# drivers.net
KiCad netlist of a schematic drawn in Altium Designer
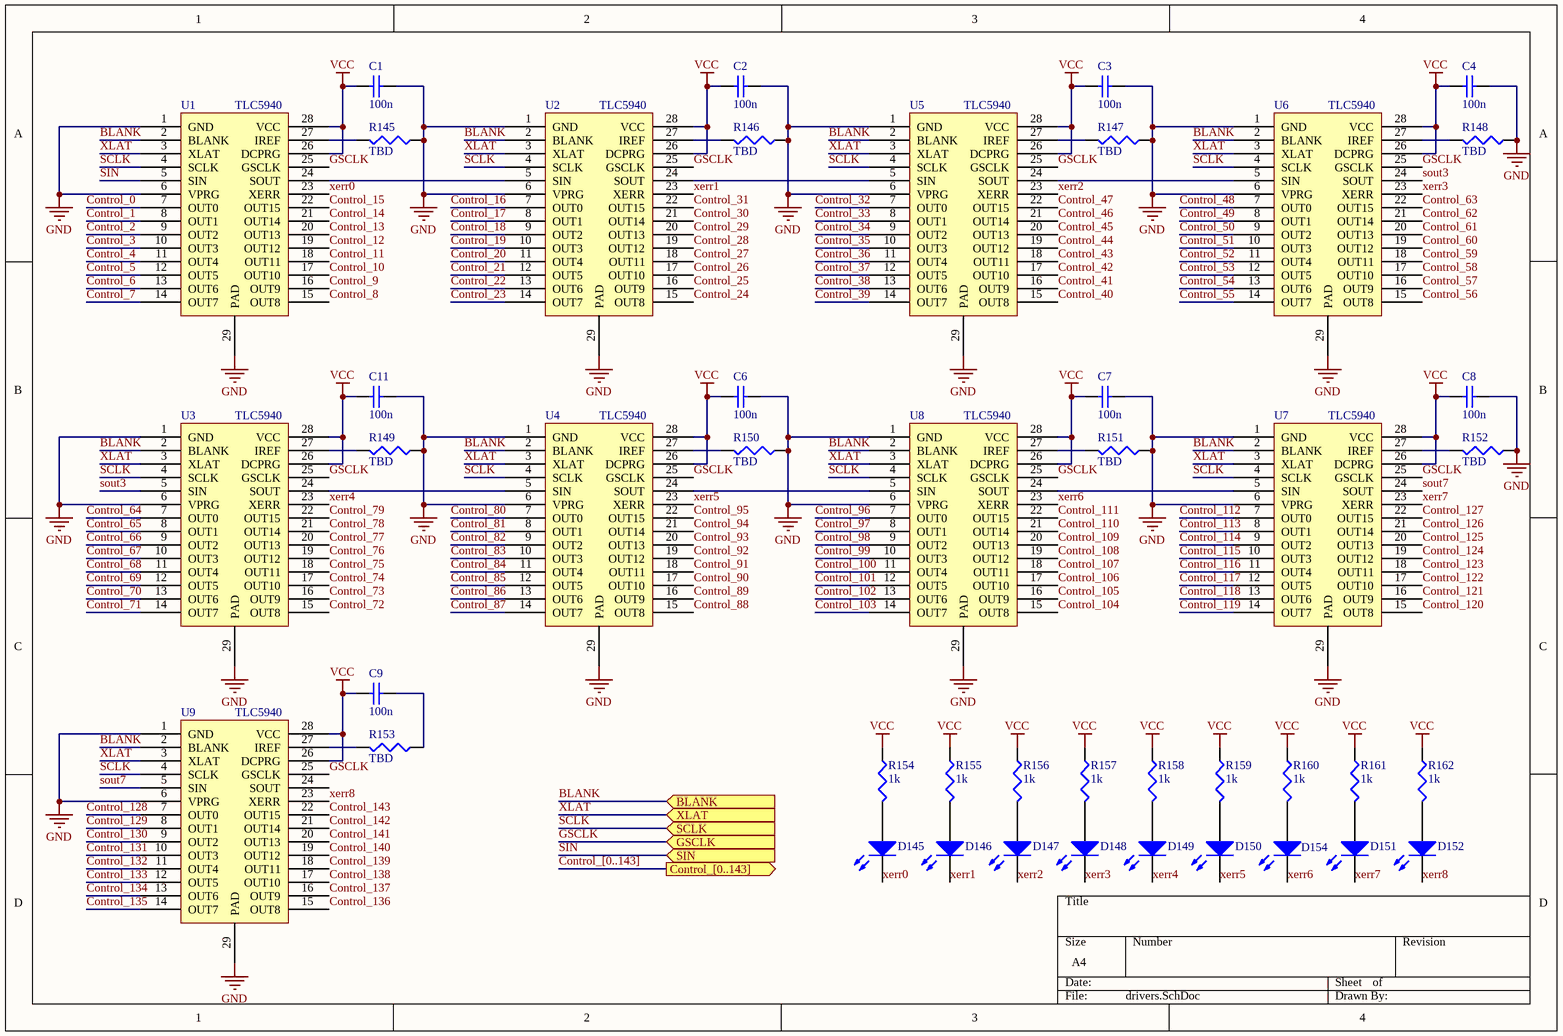
[diagram p0: drivers.SchDoc]

(export (version "E")
  (design (tool "Eeschema 10.0.6"))
  (components
    (comp (ref "C1")
      (value "100n")
      (footprint "1608[0603]")
      (description "Capacitor (Semiconductor SIM Model)")
      (fields (field (name "Comment") "Cap Semi") (field (name "PUBLISHER") "Altium Limited"))
      (libsource (lib "Miscellaneous Devices") (part "Cap Semi"))
    )
    (comp (ref "C2")
      (value "100n")
      (footprint "1608[0603]")
      (description "Capacitor (Semiconductor SIM Model)")
      (fields (field (name "Comment") "Cap Semi") (field (name "PUBLISHER") "Altium Limited"))
      (libsource (lib "Miscellaneous Devices") (part "Cap Semi"))
    )
    (comp (ref "C3")
      (value "100n")
      (footprint "1608[0603]")
      (description "Capacitor (Semiconductor SIM Model)")
      (fields (field (name "Comment") "Cap Semi") (field (name "PUBLISHER") "Altium Limited"))
      (libsource (lib "Miscellaneous Devices") (part "Cap Semi"))
    )
    (comp (ref "C4")
      (value "100n")
      (footprint "1608[0603]")
      (description "Capacitor (Semiconductor SIM Model)")
      (fields (field (name "Comment") "Cap Semi") (field (name "PUBLISHER") "Altium Limited"))
      (libsource (lib "Miscellaneous Devices") (part "Cap Semi"))
    )
    (comp (ref "C6")
      (value "100n")
      (footprint "1608[0603]")
      (description "Capacitor (Semiconductor SIM Model)")
      (fields (field (name "Comment") "Cap Semi") (field (name "PUBLISHER") "Altium Limited"))
      (libsource (lib "Miscellaneous Devices") (part "Cap Semi"))
    )
    (comp (ref "C7")
      (value "100n")
      (footprint "1608[0603]")
      (description "Capacitor (Semiconductor SIM Model)")
      (fields (field (name "Comment") "Cap Semi") (field (name "PUBLISHER") "Altium Limited"))
      (libsource (lib "Miscellaneous Devices") (part "Cap Semi"))
    )
    (comp (ref "C8")
      (value "100n")
      (footprint "1608[0603]")
      (description "Capacitor (Semiconductor SIM Model)")
      (fields (field (name "Comment") "Cap Semi") (field (name "PUBLISHER") "Altium Limited"))
      (libsource (lib "Miscellaneous Devices") (part "Cap Semi"))
    )
    (comp (ref "C9")
      (value "100n")
      (footprint "1608[0603]")
      (description "Capacitor (Semiconductor SIM Model)")
      (fields (field (name "Comment") "Cap Semi") (field (name "PUBLISHER") "Altium Limited"))
      (libsource (lib "Miscellaneous Devices") (part "Cap Semi"))
    )
    (comp (ref "C11")
      (value "100n")
      (footprint "1608[0603]")
      (description "Capacitor (Semiconductor SIM Model)")
      (fields (field (name "Comment") "Cap Semi") (field (name "PUBLISHER") "Altium Limited"))
      (libsource (lib "Miscellaneous Devices") (part "Cap Semi"))
    )
    (comp (ref "D145")
      (value "LED0")
      (footprint "J1-0603")
      (description "Typical INFRARED GaAs LED")
      (fields (field (name "PUBLISHER") "Altium Limited"))
      (libsource (lib "Miscellaneous Devices") (part "LED0"))
    )
    (comp (ref "D146")
      (value "LED0")
      (footprint "J1-0603")
      (description "Typical INFRARED GaAs LED")
      (fields (field (name "PUBLISHER") "Altium Limited"))
      (libsource (lib "Miscellaneous Devices") (part "LED0"))
    )
    (comp (ref "D147")
      (value "LED0")
      (footprint "J1-0603")
      (description "Typical INFRARED GaAs LED")
      (fields (field (name "PUBLISHER") "Altium Limited"))
      (libsource (lib "Miscellaneous Devices") (part "LED0"))
    )
    (comp (ref "D148")
      (value "LED0")
      (footprint "J1-0603")
      (description "Typical INFRARED GaAs LED")
      (fields (field (name "PUBLISHER") "Altium Limited"))
      (libsource (lib "Miscellaneous Devices") (part "LED0"))
    )
    (comp (ref "D149")
      (value "LED0")
      (footprint "J1-0603")
      (description "Typical INFRARED GaAs LED")
      (fields (field (name "PUBLISHER") "Altium Limited"))
      (libsource (lib "Miscellaneous Devices") (part "LED0"))
    )
    (comp (ref "D150")
      (value "LED0")
      (footprint "J1-0603")
      (description "Typical INFRARED GaAs LED")
      (fields (field (name "PUBLISHER") "Altium Limited"))
      (libsource (lib "Miscellaneous Devices") (part "LED0"))
    )
    (comp (ref "D151")
      (value "LED0")
      (footprint "J1-0603")
      (description "Typical INFRARED GaAs LED")
      (fields (field (name "PUBLISHER") "Altium Limited"))
      (libsource (lib "Miscellaneous Devices") (part "LED0"))
    )
    (comp (ref "D152")
      (value "LED0")
      (footprint "J1-0603")
      (description "Typical INFRARED GaAs LED")
      (fields (field (name "PUBLISHER") "Altium Limited"))
      (libsource (lib "Miscellaneous Devices") (part "LED0"))
    )
    (comp (ref "D154")
      (value "LED0")
      (footprint "J1-0603")
      (description "Typical INFRARED GaAs LED")
      (fields (field (name "PUBLISHER") "Altium Limited"))
      (libsource (lib "Miscellaneous Devices") (part "LED0"))
    )
    (comp (ref "R145")
      (value "TBD")
      (footprint "J1-0603")
      (description "Resistor")
      (fields (field (name "Comment") "Res3") (field (name "PUBLISHER") "Altium Limited"))
      (libsource (lib "Miscellaneous Devices") (part "Res3"))
    )
    (comp (ref "R146")
      (value "TBD")
      (footprint "J1-0603")
      (description "Resistor")
      (fields (field (name "Comment") "Res3") (field (name "PUBLISHER") "Altium Limited"))
      (libsource (lib "Miscellaneous Devices") (part "Res3"))
    )
    (comp (ref "R147")
      (value "TBD")
      (footprint "J1-0603")
      (description "Resistor")
      (fields (field (name "Comment") "Res3") (field (name "PUBLISHER") "Altium Limited"))
      (libsource (lib "Miscellaneous Devices") (part "Res3"))
    )
    (comp (ref "R148")
      (value "TBD")
      (footprint "J1-0603")
      (description "Resistor")
      (fields (field (name "Comment") "Res3") (field (name "PUBLISHER") "Altium Limited"))
      (libsource (lib "Miscellaneous Devices") (part "Res3"))
    )
    (comp (ref "R149")
      (value "TBD")
      (footprint "J1-0603")
      (description "Resistor")
      (fields (field (name "Comment") "Res3") (field (name "PUBLISHER") "Altium Limited"))
      (libsource (lib "Miscellaneous Devices") (part "Res3"))
    )
    (comp (ref "R150")
      (value "TBD")
      (footprint "J1-0603")
      (description "Resistor")
      (fields (field (name "Comment") "Res3") (field (name "PUBLISHER") "Altium Limited"))
      (libsource (lib "Miscellaneous Devices") (part "Res3"))
    )
    (comp (ref "R151")
      (value "TBD")
      (footprint "J1-0603")
      (description "Resistor")
      (fields (field (name "Comment") "Res3") (field (name "PUBLISHER") "Altium Limited"))
      (libsource (lib "Miscellaneous Devices") (part "Res3"))
    )
    (comp (ref "R152")
      (value "TBD")
      (footprint "J1-0603")
      (description "Resistor")
      (fields (field (name "Comment") "Res3") (field (name "PUBLISHER") "Altium Limited"))
      (libsource (lib "Miscellaneous Devices") (part "Res3"))
    )
    (comp (ref "R153")
      (value "TBD")
      (footprint "J1-0603")
      (description "Resistor")
      (fields (field (name "Comment") "Res3") (field (name "PUBLISHER") "Altium Limited"))
      (libsource (lib "Miscellaneous Devices") (part "Res3"))
    )
    (comp (ref "R154")
      (value "1k")
      (footprint "J1-0603")
      (description "Resistor")
      (fields (field (name "Comment") "Res3") (field (name "PUBLISHER") "Altium Limited"))
      (libsource (lib "Miscellaneous Devices") (part "Res3"))
    )
    (comp (ref "R155")
      (value "1k")
      (footprint "J1-0603")
      (description "Resistor")
      (fields (field (name "Comment") "Res3") (field (name "PUBLISHER") "Altium Limited"))
      (libsource (lib "Miscellaneous Devices") (part "Res3"))
    )
    (comp (ref "R156")
      (value "1k")
      (footprint "J1-0603")
      (description "Resistor")
      (fields (field (name "Comment") "Res3") (field (name "PUBLISHER") "Altium Limited"))
      (libsource (lib "Miscellaneous Devices") (part "Res3"))
    )
    (comp (ref "R157")
      (value "1k")
      (footprint "J1-0603")
      (description "Resistor")
      (fields (field (name "Comment") "Res3") (field (name "PUBLISHER") "Altium Limited"))
      (libsource (lib "Miscellaneous Devices") (part "Res3"))
    )
    (comp (ref "R158")
      (value "1k")
      (footprint "J1-0603")
      (description "Resistor")
      (fields (field (name "Comment") "Res3") (field (name "PUBLISHER") "Altium Limited"))
      (libsource (lib "Miscellaneous Devices") (part "Res3"))
    )
    (comp (ref "R159")
      (value "1k")
      (footprint "J1-0603")
      (description "Resistor")
      (fields (field (name "Comment") "Res3") (field (name "PUBLISHER") "Altium Limited"))
      (libsource (lib "Miscellaneous Devices") (part "Res3"))
    )
    (comp (ref "R160")
      (value "1k")
      (footprint "J1-0603")
      (description "Resistor")
      (fields (field (name "Comment") "Res3") (field (name "PUBLISHER") "Altium Limited"))
      (libsource (lib "Miscellaneous Devices") (part "Res3"))
    )
    (comp (ref "R161")
      (value "1k")
      (footprint "J1-0603")
      (description "Resistor")
      (fields (field (name "Comment") "Res3") (field (name "PUBLISHER") "Altium Limited"))
      (libsource (lib "Miscellaneous Devices") (part "Res3"))
    )
    (comp (ref "R162")
      (value "1k")
      (footprint "J1-0603")
      (description "Resistor")
      (fields (field (name "Comment") "Res3") (field (name "PUBLISHER") "Altium Limited"))
      (libsource (lib "Miscellaneous Devices") (part "Res3"))
    )
    (comp (ref "U1")
      (value "TLC5940")
      (footprint "HTSSOP28")
      (description "16 CHANNEL LED DRIVER WITH DOT CORRECTION AND GRAYSCALE PWM CONTROL")
      (fields (field (name "PART NUMBER") "1755256"))
      (libsource (lib "tech-thing") (part "TLC5940"))
    )
    (comp (ref "U2")
      (value "TLC5940")
      (footprint "HTSSOP28")
      (description "16 CHANNEL LED DRIVER WITH DOT CORRECTION AND GRAYSCALE PWM CONTROL")
      (fields (field (name "PART NUMBER") "1755256"))
      (libsource (lib "tech-thing") (part "TLC5940"))
    )
    (comp (ref "U3")
      (value "TLC5940")
      (footprint "HTSSOP28")
      (description "16 CHANNEL LED DRIVER WITH DOT CORRECTION AND GRAYSCALE PWM CONTROL")
      (fields (field (name "PART NUMBER") "1755256"))
      (libsource (lib "tech-thing") (part "TLC5940"))
    )
    (comp (ref "U4")
      (value "TLC5940")
      (footprint "HTSSOP28")
      (description "16 CHANNEL LED DRIVER WITH DOT CORRECTION AND GRAYSCALE PWM CONTROL")
      (fields (field (name "PART NUMBER") "1755256"))
      (libsource (lib "tech-thing") (part "TLC5940"))
    )
    (comp (ref "U5")
      (value "TLC5940")
      (footprint "HTSSOP28")
      (description "16 CHANNEL LED DRIVER WITH DOT CORRECTION AND GRAYSCALE PWM CONTROL")
      (fields (field (name "PART NUMBER") "1755256"))
      (libsource (lib "tech-thing") (part "TLC5940"))
    )
    (comp (ref "U6")
      (value "TLC5940")
      (footprint "HTSSOP28")
      (description "16 CHANNEL LED DRIVER WITH DOT CORRECTION AND GRAYSCALE PWM CONTROL")
      (fields (field (name "PART NUMBER") "1755256"))
      (libsource (lib "tech-thing") (part "TLC5940"))
    )
    (comp (ref "U7")
      (value "TLC5940")
      (footprint "HTSSOP28")
      (description "16 CHANNEL LED DRIVER WITH DOT CORRECTION AND GRAYSCALE PWM CONTROL")
      (fields (field (name "PART NUMBER") "1755256"))
      (libsource (lib "tech-thing") (part "TLC5940"))
    )
    (comp (ref "U8")
      (value "TLC5940")
      (footprint "HTSSOP28")
      (description "16 CHANNEL LED DRIVER WITH DOT CORRECTION AND GRAYSCALE PWM CONTROL")
      (fields (field (name "PART NUMBER") "1755256"))
      (libsource (lib "tech-thing") (part "TLC5940"))
    )
    (comp (ref "U9")
      (value "TLC5940")
      (footprint "HTSSOP28")
      (description "16 CHANNEL LED DRIVER WITH DOT CORRECTION AND GRAYSCALE PWM CONTROL")
      (fields (field (name "PART NUMBER") "1755256"))
      (libsource (lib "tech-thing") (part "TLC5940"))
    )
  )
  (nets
    (net (code "1") (name "/BLANK") (class "Default")
      (node (ref "U1") (pin "2") (pinfunction "BLANK_2") (pintype "passive"))
      (node (ref "U2") (pin "2") (pinfunction "BLANK_2") (pintype "passive"))
      (node (ref "U3") (pin "2") (pinfunction "BLANK_2") (pintype "passive"))
      (node (ref "U4") (pin "2") (pinfunction "BLANK_2") (pintype "passive"))
      (node (ref "U5") (pin "2") (pinfunction "BLANK_2") (pintype "passive"))
      (node (ref "U6") (pin "2") (pinfunction "BLANK_2") (pintype "passive"))
      (node (ref "U7") (pin "2") (pinfunction "BLANK_2") (pintype "passive"))
      (node (ref "U8") (pin "2") (pinfunction "BLANK_2") (pintype "passive"))
      (node (ref "U9") (pin "2") (pinfunction "BLANK_2") (pintype "passive"))
    )
    (net (code "2") (name "/Control_0") (class "Default")
      (node (ref "U1") (pin "7") (pinfunction "OUT0_7") (pintype "passive"))
    )
    (net (code "3") (name "/Control_1") (class "Default")
      (node (ref "U1") (pin "8") (pinfunction "OUT1_8") (pintype "passive"))
    )
    (net (code "4") (name "/Control_2") (class "Default")
      (node (ref "U1") (pin "9") (pinfunction "OUT2_9") (pintype "passive"))
    )
    (net (code "5") (name "/Control_3") (class "Default")
      (node (ref "U1") (pin "10") (pinfunction "OUT3_10") (pintype "passive"))
    )
    (net (code "6") (name "/Control_4") (class "Default")
      (node (ref "U1") (pin "11") (pinfunction "OUT4_11") (pintype "passive"))
    )
    (net (code "7") (name "/Control_5") (class "Default")
      (node (ref "U1") (pin "12") (pinfunction "OUT5_12") (pintype "passive"))
    )
    (net (code "8") (name "/Control_6") (class "Default")
      (node (ref "U1") (pin "13") (pinfunction "OUT6_13") (pintype "passive"))
    )
    (net (code "9") (name "/Control_7") (class "Default")
      (node (ref "U1") (pin "14") (pinfunction "OUT7_14") (pintype "passive"))
    )
    (net (code "10") (name "/Control_8") (class "Default")
      (node (ref "U1") (pin "15") (pinfunction "OUT8_15") (pintype "passive"))
    )
    (net (code "11") (name "/Control_9") (class "Default")
      (node (ref "U1") (pin "16") (pinfunction "OUT9_16") (pintype "passive"))
    )
    (net (code "12") (name "/Control_10") (class "Default")
      (node (ref "U1") (pin "17") (pinfunction "OUT10_17") (pintype "passive"))
    )
    (net (code "13") (name "/Control_11") (class "Default")
      (node (ref "U1") (pin "18") (pinfunction "OUT11_18") (pintype "passive"))
    )
    (net (code "14") (name "/Control_12") (class "Default")
      (node (ref "U1") (pin "19") (pinfunction "OUT12_19") (pintype "passive"))
    )
    (net (code "15") (name "/Control_13") (class "Default")
      (node (ref "U1") (pin "20") (pinfunction "OUT13_20") (pintype "passive"))
    )
    (net (code "16") (name "/Control_14") (class "Default")
      (node (ref "U1") (pin "21") (pinfunction "OUT14_21") (pintype "passive"))
    )
    (net (code "17") (name "/Control_15") (class "Default")
      (node (ref "U1") (pin "22") (pinfunction "OUT15_22") (pintype "passive"))
    )
    (net (code "18") (name "/Control_16") (class "Default")
      (node (ref "U2") (pin "7") (pinfunction "OUT0_7") (pintype "passive"))
    )
    (net (code "19") (name "/Control_17") (class "Default")
      (node (ref "U2") (pin "8") (pinfunction "OUT1_8") (pintype "passive"))
    )
    (net (code "20") (name "/Control_18") (class "Default")
      (node (ref "U2") (pin "9") (pinfunction "OUT2_9") (pintype "passive"))
    )
    (net (code "21") (name "/Control_19") (class "Default")
      (node (ref "U2") (pin "10") (pinfunction "OUT3_10") (pintype "passive"))
    )
    (net (code "22") (name "/Control_20") (class "Default")
      (node (ref "U2") (pin "11") (pinfunction "OUT4_11") (pintype "passive"))
    )
    (net (code "23") (name "/Control_21") (class "Default")
      (node (ref "U2") (pin "12") (pinfunction "OUT5_12") (pintype "passive"))
    )
    (net (code "24") (name "/Control_22") (class "Default")
      (node (ref "U2") (pin "13") (pinfunction "OUT6_13") (pintype "passive"))
    )
    (net (code "25") (name "/Control_23") (class "Default")
      (node (ref "U2") (pin "14") (pinfunction "OUT7_14") (pintype "passive"))
    )
    (net (code "26") (name "/Control_24") (class "Default")
      (node (ref "U2") (pin "15") (pinfunction "OUT8_15") (pintype "passive"))
    )
    (net (code "27") (name "/Control_25") (class "Default")
      (node (ref "U2") (pin "16") (pinfunction "OUT9_16") (pintype "passive"))
    )
    (net (code "28") (name "/Control_26") (class "Default")
      (node (ref "U2") (pin "17") (pinfunction "OUT10_17") (pintype "passive"))
    )
    (net (code "29") (name "/Control_27") (class "Default")
      (node (ref "U2") (pin "18") (pinfunction "OUT11_18") (pintype "passive"))
    )
    (net (code "30") (name "/Control_28") (class "Default")
      (node (ref "U2") (pin "19") (pinfunction "OUT12_19") (pintype "passive"))
    )
    (net (code "31") (name "/Control_29") (class "Default")
      (node (ref "U2") (pin "20") (pinfunction "OUT13_20") (pintype "passive"))
    )
    (net (code "32") (name "/Control_30") (class "Default")
      (node (ref "U2") (pin "21") (pinfunction "OUT14_21") (pintype "passive"))
    )
    (net (code "33") (name "/Control_31") (class "Default")
      (node (ref "U2") (pin "22") (pinfunction "OUT15_22") (pintype "passive"))
    )
    (net (code "34") (name "/Control_32") (class "Default")
      (node (ref "U5") (pin "7") (pinfunction "OUT0_7") (pintype "passive"))
    )
    (net (code "35") (name "/Control_33") (class "Default")
      (node (ref "U5") (pin "8") (pinfunction "OUT1_8") (pintype "passive"))
    )
    (net (code "36") (name "/Control_34") (class "Default")
      (node (ref "U5") (pin "9") (pinfunction "OUT2_9") (pintype "passive"))
    )
    (net (code "37") (name "/Control_35") (class "Default")
      (node (ref "U5") (pin "10") (pinfunction "OUT3_10") (pintype "passive"))
    )
    (net (code "38") (name "/Control_36") (class "Default")
      (node (ref "U5") (pin "11") (pinfunction "OUT4_11") (pintype "passive"))
    )
    (net (code "39") (name "/Control_37") (class "Default")
      (node (ref "U5") (pin "12") (pinfunction "OUT5_12") (pintype "passive"))
    )
    (net (code "40") (name "/Control_38") (class "Default")
      (node (ref "U5") (pin "13") (pinfunction "OUT6_13") (pintype "passive"))
    )
    (net (code "41") (name "/Control_39") (class "Default")
      (node (ref "U5") (pin "14") (pinfunction "OUT7_14") (pintype "passive"))
    )
    (net (code "42") (name "/Control_40") (class "Default")
      (node (ref "U5") (pin "15") (pinfunction "OUT8_15") (pintype "passive"))
    )
    (net (code "43") (name "/Control_41") (class "Default")
      (node (ref "U5") (pin "16") (pinfunction "OUT9_16") (pintype "passive"))
    )
    (net (code "44") (name "/Control_42") (class "Default")
      (node (ref "U5") (pin "17") (pinfunction "OUT10_17") (pintype "passive"))
    )
    (net (code "45") (name "/Control_43") (class "Default")
      (node (ref "U5") (pin "18") (pinfunction "OUT11_18") (pintype "passive"))
    )
    (net (code "46") (name "/Control_44") (class "Default")
      (node (ref "U5") (pin "19") (pinfunction "OUT12_19") (pintype "passive"))
    )
    (net (code "47") (name "/Control_45") (class "Default")
      (node (ref "U5") (pin "20") (pinfunction "OUT13_20") (pintype "passive"))
    )
    (net (code "48") (name "/Control_46") (class "Default")
      (node (ref "U5") (pin "21") (pinfunction "OUT14_21") (pintype "passive"))
    )
    (net (code "49") (name "/Control_47") (class "Default")
      (node (ref "U5") (pin "22") (pinfunction "OUT15_22") (pintype "passive"))
    )
    (net (code "50") (name "/Control_48") (class "Default")
      (node (ref "U6") (pin "7") (pinfunction "OUT0_7") (pintype "passive"))
    )
    (net (code "51") (name "/Control_49") (class "Default")
      (node (ref "U6") (pin "8") (pinfunction "OUT1_8") (pintype "passive"))
    )
    (net (code "52") (name "/Control_50") (class "Default")
      (node (ref "U6") (pin "9") (pinfunction "OUT2_9") (pintype "passive"))
    )
    (net (code "53") (name "/Control_51") (class "Default")
      (node (ref "U6") (pin "10") (pinfunction "OUT3_10") (pintype "passive"))
    )
    (net (code "54") (name "/Control_52") (class "Default")
      (node (ref "U6") (pin "11") (pinfunction "OUT4_11") (pintype "passive"))
    )
    (net (code "55") (name "/Control_53") (class "Default")
      (node (ref "U6") (pin "12") (pinfunction "OUT5_12") (pintype "passive"))
    )
    (net (code "56") (name "/Control_54") (class "Default")
      (node (ref "U6") (pin "13") (pinfunction "OUT6_13") (pintype "passive"))
    )
    (net (code "57") (name "/Control_55") (class "Default")
      (node (ref "U6") (pin "14") (pinfunction "OUT7_14") (pintype "passive"))
    )
    (net (code "58") (name "/Control_56") (class "Default")
      (node (ref "U6") (pin "15") (pinfunction "OUT8_15") (pintype "passive"))
    )
    (net (code "59") (name "/Control_57") (class "Default")
      (node (ref "U6") (pin "16") (pinfunction "OUT9_16") (pintype "passive"))
    )
    (net (code "60") (name "/Control_58") (class "Default")
      (node (ref "U6") (pin "17") (pinfunction "OUT10_17") (pintype "passive"))
    )
    (net (code "61") (name "/Control_59") (class "Default")
      (node (ref "U6") (pin "18") (pinfunction "OUT11_18") (pintype "passive"))
    )
    (net (code "62") (name "/Control_60") (class "Default")
      (node (ref "U6") (pin "19") (pinfunction "OUT12_19") (pintype "passive"))
    )
    (net (code "63") (name "/Control_61") (class "Default")
      (node (ref "U6") (pin "20") (pinfunction "OUT13_20") (pintype "passive"))
    )
    (net (code "64") (name "/Control_62") (class "Default")
      (node (ref "U6") (pin "21") (pinfunction "OUT14_21") (pintype "passive"))
    )
    (net (code "65") (name "/Control_63") (class "Default")
      (node (ref "U6") (pin "22") (pinfunction "OUT15_22") (pintype "passive"))
    )
    (net (code "66") (name "/Control_64") (class "Default")
      (node (ref "U3") (pin "7") (pinfunction "OUT0_7") (pintype "passive"))
    )
    (net (code "67") (name "/Control_65") (class "Default")
      (node (ref "U3") (pin "8") (pinfunction "OUT1_8") (pintype "passive"))
    )
    (net (code "68") (name "/Control_66") (class "Default")
      (node (ref "U3") (pin "9") (pinfunction "OUT2_9") (pintype "passive"))
    )
    (net (code "69") (name "/Control_67") (class "Default")
      (node (ref "U3") (pin "10") (pinfunction "OUT3_10") (pintype "passive"))
    )
    (net (code "70") (name "/Control_68") (class "Default")
      (node (ref "U3") (pin "11") (pinfunction "OUT4_11") (pintype "passive"))
    )
    (net (code "71") (name "/Control_69") (class "Default")
      (node (ref "U3") (pin "12") (pinfunction "OUT5_12") (pintype "passive"))
    )
    (net (code "72") (name "/Control_70") (class "Default")
      (node (ref "U3") (pin "13") (pinfunction "OUT6_13") (pintype "passive"))
    )
    (net (code "73") (name "/Control_71") (class "Default")
      (node (ref "U3") (pin "14") (pinfunction "OUT7_14") (pintype "passive"))
    )
    (net (code "74") (name "/Control_72") (class "Default")
      (node (ref "U3") (pin "15") (pinfunction "OUT8_15") (pintype "passive"))
    )
    (net (code "75") (name "/Control_73") (class "Default")
      (node (ref "U3") (pin "16") (pinfunction "OUT9_16") (pintype "passive"))
    )
    (net (code "76") (name "/Control_74") (class "Default")
      (node (ref "U3") (pin "17") (pinfunction "OUT10_17") (pintype "passive"))
    )
    (net (code "77") (name "/Control_75") (class "Default")
      (node (ref "U3") (pin "18") (pinfunction "OUT11_18") (pintype "passive"))
    )
    (net (code "78") (name "/Control_76") (class "Default")
      (node (ref "U3") (pin "19") (pinfunction "OUT12_19") (pintype "passive"))
    )
    (net (code "79") (name "/Control_77") (class "Default")
      (node (ref "U3") (pin "20") (pinfunction "OUT13_20") (pintype "passive"))
    )
    (net (code "80") (name "/Control_78") (class "Default")
      (node (ref "U3") (pin "21") (pinfunction "OUT14_21") (pintype "passive"))
    )
    (net (code "81") (name "/Control_79") (class "Default")
      (node (ref "U3") (pin "22") (pinfunction "OUT15_22") (pintype "passive"))
    )
    (net (code "82") (name "/Control_80") (class "Default")
      (node (ref "U4") (pin "7") (pinfunction "OUT0_7") (pintype "passive"))
    )
    (net (code "83") (name "/Control_81") (class "Default")
      (node (ref "U4") (pin "8") (pinfunction "OUT1_8") (pintype "passive"))
    )
    (net (code "84") (name "/Control_82") (class "Default")
      (node (ref "U4") (pin "9") (pinfunction "OUT2_9") (pintype "passive"))
    )
    (net (code "85") (name "/Control_83") (class "Default")
      (node (ref "U4") (pin "10") (pinfunction "OUT3_10") (pintype "passive"))
    )
    (net (code "86") (name "/Control_84") (class "Default")
      (node (ref "U4") (pin "11") (pinfunction "OUT4_11") (pintype "passive"))
    )
    (net (code "87") (name "/Control_85") (class "Default")
      (node (ref "U4") (pin "12") (pinfunction "OUT5_12") (pintype "passive"))
    )
    (net (code "88") (name "/Control_86") (class "Default")
      (node (ref "U4") (pin "13") (pinfunction "OUT6_13") (pintype "passive"))
    )
    (net (code "89") (name "/Control_87") (class "Default")
      (node (ref "U4") (pin "14") (pinfunction "OUT7_14") (pintype "passive"))
    )
    (net (code "90") (name "/Control_88") (class "Default")
      (node (ref "U4") (pin "15") (pinfunction "OUT8_15") (pintype "passive"))
    )
    (net (code "91") (name "/Control_89") (class "Default")
      (node (ref "U4") (pin "16") (pinfunction "OUT9_16") (pintype "passive"))
    )
    (net (code "92") (name "/Control_90") (class "Default")
      (node (ref "U4") (pin "17") (pinfunction "OUT10_17") (pintype "passive"))
    )
    (net (code "93") (name "/Control_91") (class "Default")
      (node (ref "U4") (pin "18") (pinfunction "OUT11_18") (pintype "passive"))
    )
    (net (code "94") (name "/Control_92") (class "Default")
      (node (ref "U4") (pin "19") (pinfunction "OUT12_19") (pintype "passive"))
    )
    (net (code "95") (name "/Control_93") (class "Default")
      (node (ref "U4") (pin "20") (pinfunction "OUT13_20") (pintype "passive"))
    )
    (net (code "96") (name "/Control_94") (class "Default")
      (node (ref "U4") (pin "21") (pinfunction "OUT14_21") (pintype "passive"))
    )
    (net (code "97") (name "/Control_95") (class "Default")
      (node (ref "U4") (pin "22") (pinfunction "OUT15_22") (pintype "passive"))
    )
    (net (code "98") (name "/Control_96") (class "Default")
      (node (ref "U8") (pin "7") (pinfunction "OUT0_7") (pintype "passive"))
    )
    (net (code "99") (name "/Control_97") (class "Default")
      (node (ref "U8") (pin "8") (pinfunction "OUT1_8") (pintype "passive"))
    )
    (net (code "100") (name "/Control_98") (class "Default")
      (node (ref "U8") (pin "9") (pinfunction "OUT2_9") (pintype "passive"))
    )
    (net (code "101") (name "/Control_99") (class "Default")
      (node (ref "U8") (pin "10") (pinfunction "OUT3_10") (pintype "passive"))
    )
    (net (code "102") (name "/Control_100") (class "Default")
      (node (ref "U8") (pin "11") (pinfunction "OUT4_11") (pintype "passive"))
    )
    (net (code "103") (name "/Control_101") (class "Default")
      (node (ref "U8") (pin "12") (pinfunction "OUT5_12") (pintype "passive"))
    )
    (net (code "104") (name "/Control_102") (class "Default")
      (node (ref "U8") (pin "13") (pinfunction "OUT6_13") (pintype "passive"))
    )
    (net (code "105") (name "/Control_103") (class "Default")
      (node (ref "U8") (pin "14") (pinfunction "OUT7_14") (pintype "passive"))
    )
    (net (code "106") (name "/Control_104") (class "Default")
      (node (ref "U8") (pin "15") (pinfunction "OUT8_15") (pintype "passive"))
    )
    (net (code "107") (name "/Control_105") (class "Default")
      (node (ref "U8") (pin "16") (pinfunction "OUT9_16") (pintype "passive"))
    )
    (net (code "108") (name "/Control_106") (class "Default")
      (node (ref "U8") (pin "17") (pinfunction "OUT10_17") (pintype "passive"))
    )
    (net (code "109") (name "/Control_107") (class "Default")
      (node (ref "U8") (pin "18") (pinfunction "OUT11_18") (pintype "passive"))
    )
    (net (code "110") (name "/Control_108") (class "Default")
      (node (ref "U8") (pin "19") (pinfunction "OUT12_19") (pintype "passive"))
    )
    (net (code "111") (name "/Control_109") (class "Default")
      (node (ref "U8") (pin "20") (pinfunction "OUT13_20") (pintype "passive"))
    )
    (net (code "112") (name "/Control_110") (class "Default")
      (node (ref "U8") (pin "21") (pinfunction "OUT14_21") (pintype "passive"))
    )
    (net (code "113") (name "/Control_111") (class "Default")
      (node (ref "U8") (pin "22") (pinfunction "OUT15_22") (pintype "passive"))
    )
    (net (code "114") (name "/Control_112") (class "Default")
      (node (ref "U7") (pin "7") (pinfunction "OUT0_7") (pintype "passive"))
    )
    (net (code "115") (name "/Control_113") (class "Default")
      (node (ref "U7") (pin "8") (pinfunction "OUT1_8") (pintype "passive"))
    )
    (net (code "116") (name "/Control_114") (class "Default")
      (node (ref "U7") (pin "9") (pinfunction "OUT2_9") (pintype "passive"))
    )
    (net (code "117") (name "/Control_115") (class "Default")
      (node (ref "U7") (pin "10") (pinfunction "OUT3_10") (pintype "passive"))
    )
    (net (code "118") (name "/Control_116") (class "Default")
      (node (ref "U7") (pin "11") (pinfunction "OUT4_11") (pintype "passive"))
    )
    (net (code "119") (name "/Control_117") (class "Default")
      (node (ref "U7") (pin "12") (pinfunction "OUT5_12") (pintype "passive"))
    )
    (net (code "120") (name "/Control_118") (class "Default")
      (node (ref "U7") (pin "13") (pinfunction "OUT6_13") (pintype "passive"))
    )
    (net (code "121") (name "/Control_119") (class "Default")
      (node (ref "U7") (pin "14") (pinfunction "OUT7_14") (pintype "passive"))
    )
    (net (code "122") (name "/Control_120") (class "Default")
      (node (ref "U7") (pin "15") (pinfunction "OUT8_15") (pintype "passive"))
    )
    (net (code "123") (name "/Control_121") (class "Default")
      (node (ref "U7") (pin "16") (pinfunction "OUT9_16") (pintype "passive"))
    )
    (net (code "124") (name "/Control_122") (class "Default")
      (node (ref "U7") (pin "17") (pinfunction "OUT10_17") (pintype "passive"))
    )
    (net (code "125") (name "/Control_123") (class "Default")
      (node (ref "U7") (pin "18") (pinfunction "OUT11_18") (pintype "passive"))
    )
    (net (code "126") (name "/Control_124") (class "Default")
      (node (ref "U7") (pin "19") (pinfunction "OUT12_19") (pintype "passive"))
    )
    (net (code "127") (name "/Control_125") (class "Default")
      (node (ref "U7") (pin "20") (pinfunction "OUT13_20") (pintype "passive"))
    )
    (net (code "128") (name "/Control_126") (class "Default")
      (node (ref "U7") (pin "21") (pinfunction "OUT14_21") (pintype "passive"))
    )
    (net (code "129") (name "/Control_127") (class "Default")
      (node (ref "U7") (pin "22") (pinfunction "OUT15_22") (pintype "passive"))
    )
    (net (code "130") (name "/Control_128") (class "Default")
      (node (ref "U9") (pin "7") (pinfunction "OUT0_7") (pintype "passive"))
    )
    (net (code "131") (name "/Control_129") (class "Default")
      (node (ref "U9") (pin "8") (pinfunction "OUT1_8") (pintype "passive"))
    )
    (net (code "132") (name "/Control_130") (class "Default")
      (node (ref "U9") (pin "9") (pinfunction "OUT2_9") (pintype "passive"))
    )
    (net (code "133") (name "/Control_131") (class "Default")
      (node (ref "U9") (pin "10") (pinfunction "OUT3_10") (pintype "passive"))
    )
    (net (code "134") (name "/Control_132") (class "Default")
      (node (ref "U9") (pin "11") (pinfunction "OUT4_11") (pintype "passive"))
    )
    (net (code "135") (name "/Control_133") (class "Default")
      (node (ref "U9") (pin "12") (pinfunction "OUT5_12") (pintype "passive"))
    )
    (net (code "136") (name "/Control_134") (class "Default")
      (node (ref "U9") (pin "13") (pinfunction "OUT6_13") (pintype "passive"))
    )
    (net (code "137") (name "/Control_135") (class "Default")
      (node (ref "U9") (pin "14") (pinfunction "OUT7_14") (pintype "passive"))
    )
    (net (code "138") (name "/Control_136") (class "Default")
      (node (ref "U9") (pin "15") (pinfunction "OUT8_15") (pintype "passive"))
    )
    (net (code "139") (name "/Control_137") (class "Default")
      (node (ref "U9") (pin "16") (pinfunction "OUT9_16") (pintype "passive"))
    )
    (net (code "140") (name "/Control_138") (class "Default")
      (node (ref "U9") (pin "17") (pinfunction "OUT10_17") (pintype "passive"))
    )
    (net (code "141") (name "/Control_139") (class "Default")
      (node (ref "U9") (pin "18") (pinfunction "OUT11_18") (pintype "passive"))
    )
    (net (code "142") (name "/Control_140") (class "Default")
      (node (ref "U9") (pin "19") (pinfunction "OUT12_19") (pintype "passive"))
    )
    (net (code "143") (name "/Control_141") (class "Default")
      (node (ref "U9") (pin "20") (pinfunction "OUT13_20") (pintype "passive"))
    )
    (net (code "144") (name "/Control_142") (class "Default")
      (node (ref "U9") (pin "21") (pinfunction "OUT14_21") (pintype "passive"))
    )
    (net (code "145") (name "/Control_143") (class "Default")
      (node (ref "U9") (pin "22") (pinfunction "OUT15_22") (pintype "passive"))
    )
    (net (code "147") (name "/GSCLK") (class "Default")
      (node (ref "U1") (pin "25") (pinfunction "GSCLK_25") (pintype "passive"))
      (node (ref "U2") (pin "25") (pinfunction "GSCLK_25") (pintype "passive"))
      (node (ref "U3") (pin "25") (pinfunction "GSCLK_25") (pintype "passive"))
      (node (ref "U4") (pin "25") (pinfunction "GSCLK_25") (pintype "passive"))
      (node (ref "U5") (pin "25") (pinfunction "GSCLK_25") (pintype "passive"))
      (node (ref "U6") (pin "25") (pinfunction "GSCLK_25") (pintype "passive"))
      (node (ref "U7") (pin "25") (pinfunction "GSCLK_25") (pintype "passive"))
      (node (ref "U8") (pin "25") (pinfunction "GSCLK_25") (pintype "passive"))
      (node (ref "U9") (pin "25") (pinfunction "GSCLK_25") (pintype "passive"))
    )
    (net (code "148") (name "/SCLK") (class "Default")
      (node (ref "U1") (pin "4") (pinfunction "SCLK_4") (pintype "passive"))
      (node (ref "U2") (pin "4") (pinfunction "SCLK_4") (pintype "passive"))
      (node (ref "U3") (pin "4") (pinfunction "SCLK_4") (pintype "passive"))
      (node (ref "U4") (pin "4") (pinfunction "SCLK_4") (pintype "passive"))
      (node (ref "U5") (pin "4") (pinfunction "SCLK_4") (pintype "passive"))
      (node (ref "U6") (pin "4") (pinfunction "SCLK_4") (pintype "passive"))
      (node (ref "U7") (pin "4") (pinfunction "SCLK_4") (pintype "passive"))
      (node (ref "U8") (pin "4") (pinfunction "SCLK_4") (pintype "passive"))
      (node (ref "U9") (pin "4") (pinfunction "SCLK_4") (pintype "passive"))
    )
    (net (code "149") (name "/SIN") (class "Default")
      (node (ref "U1") (pin "5") (pinfunction "SIN_5") (pintype "passive"))
    )
    (net (code "150") (name "/XLAT") (class "Default")
      (node (ref "U1") (pin "3") (pinfunction "XLAT_3") (pintype "passive"))
      (node (ref "U2") (pin "3") (pinfunction "XLAT_3") (pintype "passive"))
      (node (ref "U3") (pin "3") (pinfunction "XLAT_3") (pintype "passive"))
      (node (ref "U4") (pin "3") (pinfunction "XLAT_3") (pintype "passive"))
      (node (ref "U5") (pin "3") (pinfunction "XLAT_3") (pintype "passive"))
      (node (ref "U6") (pin "3") (pinfunction "XLAT_3") (pintype "passive"))
      (node (ref "U7") (pin "3") (pinfunction "XLAT_3") (pintype "passive"))
      (node (ref "U8") (pin "3") (pinfunction "XLAT_3") (pintype "passive"))
      (node (ref "U9") (pin "3") (pinfunction "XLAT_3") (pintype "passive"))
    )
    (net (code "151") (name "/sout3") (class "Default")
      (node (ref "U3") (pin "5") (pinfunction "SIN_5") (pintype "passive"))
      (node (ref "U6") (pin "24") (pinfunction "SOUT_24") (pintype "passive"))
    )
    (net (code "152") (name "/sout7") (class "Default")
      (node (ref "U7") (pin "24") (pinfunction "SOUT_24") (pintype "passive"))
      (node (ref "U9") (pin "5") (pinfunction "SIN_5") (pintype "passive"))
    )
    (net (code "153") (name "/xerr0") (class "Default")
      (node (ref "D145") (pin "2") (pinfunction "K_2") (pintype "passive"))
      (node (ref "U1") (pin "23") (pinfunction "XERR_23") (pintype "passive"))
    )
    (net (code "154") (name "/xerr1") (class "Default")
      (node (ref "D146") (pin "2") (pinfunction "K_2") (pintype "passive"))
      (node (ref "U2") (pin "23") (pinfunction "XERR_23") (pintype "passive"))
    )
    (net (code "155") (name "/xerr2") (class "Default")
      (node (ref "D147") (pin "2") (pinfunction "K_2") (pintype "passive"))
      (node (ref "U5") (pin "23") (pinfunction "XERR_23") (pintype "passive"))
    )
    (net (code "156") (name "/xerr3") (class "Default")
      (node (ref "D148") (pin "2") (pinfunction "K_2") (pintype "passive"))
      (node (ref "U6") (pin "23") (pinfunction "XERR_23") (pintype "passive"))
    )
    (net (code "157") (name "/xerr4") (class "Default")
      (node (ref "D149") (pin "2") (pinfunction "K_2") (pintype "passive"))
      (node (ref "U3") (pin "23") (pinfunction "XERR_23") (pintype "passive"))
    )
    (net (code "158") (name "/xerr5") (class "Default")
      (node (ref "D150") (pin "2") (pinfunction "K_2") (pintype "passive"))
      (node (ref "U4") (pin "23") (pinfunction "XERR_23") (pintype "passive"))
    )
    (net (code "159") (name "/xerr6") (class "Default")
      (node (ref "D154") (pin "2") (pinfunction "K_2") (pintype "passive"))
      (node (ref "U8") (pin "23") (pinfunction "XERR_23") (pintype "passive"))
    )
    (net (code "160") (name "/xerr7") (class "Default")
      (node (ref "D151") (pin "2") (pinfunction "K_2") (pintype "passive"))
      (node (ref "U7") (pin "23") (pinfunction "XERR_23") (pintype "passive"))
    )
    (net (code "161") (name "/xerr8") (class "Default")
      (node (ref "D152") (pin "2") (pinfunction "K_2") (pintype "passive"))
      (node (ref "U9") (pin "23") (pinfunction "XERR_23") (pintype "passive"))
    )
    (net (code "162") (name "GND") (class "Default")
      (node (ref "C1") (pin "1") (pinfunction "1_1") (pintype "passive"))
      (node (ref "C11") (pin "1") (pinfunction "1_1") (pintype "passive"))
      (node (ref "C2") (pin "1") (pinfunction "1_1") (pintype "passive"))
      (node (ref "C3") (pin "1") (pinfunction "1_1") (pintype "passive"))
      (node (ref "C4") (pin "1") (pinfunction "1_1") (pintype "passive"))
      (node (ref "C6") (pin "1") (pinfunction "1_1") (pintype "passive"))
      (node (ref "C7") (pin "1") (pinfunction "1_1") (pintype "passive"))
      (node (ref "C8") (pin "1") (pinfunction "1_1") (pintype "passive"))
      (node (ref "R145") (pin "1") (pinfunction "1_1") (pintype "passive"))
      (node (ref "R146") (pin "1") (pinfunction "1_1") (pintype "passive"))
      (node (ref "R147") (pin "1") (pinfunction "1_1") (pintype "passive"))
      (node (ref "R148") (pin "1") (pinfunction "1_1") (pintype "passive"))
      (node (ref "R149") (pin "1") (pinfunction "1_1") (pintype "passive"))
      (node (ref "R150") (pin "1") (pinfunction "1_1") (pintype "passive"))
      (node (ref "R151") (pin "1") (pinfunction "1_1") (pintype "passive"))
      (node (ref "R152") (pin "1") (pinfunction "1_1") (pintype "passive"))
      (node (ref "U1") (pin "1") (pinfunction "GND_1") (pintype "passive"))
      (node (ref "U1") (pin "29") (pinfunction "PAD_29") (pintype "passive"))
      (node (ref "U1") (pin "6") (pinfunction "VPRG_6") (pintype "passive"))
      (node (ref "U2") (pin "1") (pinfunction "GND_1") (pintype "passive"))
      (node (ref "U2") (pin "29") (pinfunction "PAD_29") (pintype "passive"))
      (node (ref "U2") (pin "6") (pinfunction "VPRG_6") (pintype "passive"))
      (node (ref "U3") (pin "1") (pinfunction "GND_1") (pintype "passive"))
      (node (ref "U3") (pin "29") (pinfunction "PAD_29") (pintype "passive"))
      (node (ref "U3") (pin "6") (pinfunction "VPRG_6") (pintype "passive"))
      (node (ref "U4") (pin "1") (pinfunction "GND_1") (pintype "passive"))
      (node (ref "U4") (pin "29") (pinfunction "PAD_29") (pintype "passive"))
      (node (ref "U4") (pin "6") (pinfunction "VPRG_6") (pintype "passive"))
      (node (ref "U5") (pin "1") (pinfunction "GND_1") (pintype "passive"))
      (node (ref "U5") (pin "29") (pinfunction "PAD_29") (pintype "passive"))
      (node (ref "U5") (pin "6") (pinfunction "VPRG_6") (pintype "passive"))
      (node (ref "U6") (pin "1") (pinfunction "GND_1") (pintype "passive"))
      (node (ref "U6") (pin "29") (pinfunction "PAD_29") (pintype "passive"))
      (node (ref "U6") (pin "6") (pinfunction "VPRG_6") (pintype "passive"))
      (node (ref "U7") (pin "1") (pinfunction "GND_1") (pintype "passive"))
      (node (ref "U7") (pin "29") (pinfunction "PAD_29") (pintype "passive"))
      (node (ref "U7") (pin "6") (pinfunction "VPRG_6") (pintype "passive"))
      (node (ref "U8") (pin "1") (pinfunction "GND_1") (pintype "passive"))
      (node (ref "U8") (pin "29") (pinfunction "PAD_29") (pintype "passive"))
      (node (ref "U8") (pin "6") (pinfunction "VPRG_6") (pintype "passive"))
      (node (ref "U9") (pin "1") (pinfunction "GND_1") (pintype "passive"))
      (node (ref "U9") (pin "29") (pinfunction "PAD_29") (pintype "passive"))
      (node (ref "U9") (pin "6") (pinfunction "VPRG_6") (pintype "passive"))
    )
    (net (code "163") (name "Net-(C9-Pad1)") (class "Default")
      (node (ref "C9") (pin "1") (pinfunction "1_1") (pintype "passive"))
      (node (ref "R153") (pin "1") (pinfunction "1_1") (pintype "passive"))
    )
    (net (code "164") (name "Net-(D145-A)") (class "Default")
      (node (ref "D145") (pin "1") (pinfunction "A_1") (pintype "passive"))
      (node (ref "R154") (pin "2") (pinfunction "2_2") (pintype "passive"))
    )
    (net (code "165") (name "Net-(D146-A)") (class "Default")
      (node (ref "D146") (pin "1") (pinfunction "A_1") (pintype "passive"))
      (node (ref "R155") (pin "2") (pinfunction "2_2") (pintype "passive"))
    )
    (net (code "166") (name "Net-(D147-A)") (class "Default")
      (node (ref "D147") (pin "1") (pinfunction "A_1") (pintype "passive"))
      (node (ref "R156") (pin "2") (pinfunction "2_2") (pintype "passive"))
    )
    (net (code "167") (name "Net-(D148-A)") (class "Default")
      (node (ref "D148") (pin "1") (pinfunction "A_1") (pintype "passive"))
      (node (ref "R157") (pin "2") (pinfunction "2_2") (pintype "passive"))
    )
    (net (code "168") (name "Net-(D149-A)") (class "Default")
      (node (ref "D149") (pin "1") (pinfunction "A_1") (pintype "passive"))
      (node (ref "R158") (pin "2") (pinfunction "2_2") (pintype "passive"))
    )
    (net (code "169") (name "Net-(D150-A)") (class "Default")
      (node (ref "D150") (pin "1") (pinfunction "A_1") (pintype "passive"))
      (node (ref "R159") (pin "2") (pinfunction "2_2") (pintype "passive"))
    )
    (net (code "170") (name "Net-(D151-A)") (class "Default")
      (node (ref "D151") (pin "1") (pinfunction "A_1") (pintype "passive"))
      (node (ref "R161") (pin "2") (pinfunction "2_2") (pintype "passive"))
    )
    (net (code "171") (name "Net-(D152-A)") (class "Default")
      (node (ref "D152") (pin "1") (pinfunction "A_1") (pintype "passive"))
      (node (ref "R162") (pin "2") (pinfunction "2_2") (pintype "passive"))
    )
    (net (code "172") (name "Net-(D154-A)") (class "Default")
      (node (ref "D154") (pin "1") (pinfunction "A_1") (pintype "passive"))
      (node (ref "R160") (pin "2") (pinfunction "2_2") (pintype "passive"))
    )
    (net (code "173") (name "Net-(U1-IREF)") (class "Default")
      (node (ref "R145") (pin "2") (pinfunction "2_2") (pintype "passive"))
      (node (ref "U1") (pin "27") (pinfunction "IREF_27") (pintype "passive"))
    )
    (net (code "174") (name "Net-(U1-SOUT)") (class "Default")
      (node (ref "U1") (pin "24") (pinfunction "SOUT_24") (pintype "passive"))
      (node (ref "U2") (pin "5") (pinfunction "SIN_5") (pintype "passive"))
    )
    (net (code "175") (name "Net-(U2-IREF)") (class "Default")
      (node (ref "R146") (pin "2") (pinfunction "2_2") (pintype "passive"))
      (node (ref "U2") (pin "27") (pinfunction "IREF_27") (pintype "passive"))
    )
    (net (code "176") (name "Net-(U2-SOUT)") (class "Default")
      (node (ref "U2") (pin "24") (pinfunction "SOUT_24") (pintype "passive"))
      (node (ref "U5") (pin "5") (pinfunction "SIN_5") (pintype "passive"))
    )
    (net (code "177") (name "Net-(U3-IREF)") (class "Default")
      (node (ref "R149") (pin "2") (pinfunction "2_2") (pintype "passive"))
      (node (ref "U3") (pin "27") (pinfunction "IREF_27") (pintype "passive"))
    )
    (net (code "178") (name "Net-(U3-SOUT)") (class "Default")
      (node (ref "U3") (pin "24") (pinfunction "SOUT_24") (pintype "passive"))
      (node (ref "U4") (pin "5") (pinfunction "SIN_5") (pintype "passive"))
    )
    (net (code "179") (name "Net-(U4-IREF)") (class "Default")
      (node (ref "R150") (pin "2") (pinfunction "2_2") (pintype "passive"))
      (node (ref "U4") (pin "27") (pinfunction "IREF_27") (pintype "passive"))
    )
    (net (code "180") (name "Net-(U4-SOUT)") (class "Default")
      (node (ref "U4") (pin "24") (pinfunction "SOUT_24") (pintype "passive"))
      (node (ref "U8") (pin "5") (pinfunction "SIN_5") (pintype "passive"))
    )
    (net (code "181") (name "Net-(U5-IREF)") (class "Default")
      (node (ref "R147") (pin "2") (pinfunction "2_2") (pintype "passive"))
      (node (ref "U5") (pin "27") (pinfunction "IREF_27") (pintype "passive"))
    )
    (net (code "182") (name "Net-(U5-SOUT)") (class "Default")
      (node (ref "U5") (pin "24") (pinfunction "SOUT_24") (pintype "passive"))
      (node (ref "U6") (pin "5") (pinfunction "SIN_5") (pintype "passive"))
    )
    (net (code "183") (name "Net-(U6-IREF)") (class "Default")
      (node (ref "R148") (pin "2") (pinfunction "2_2") (pintype "passive"))
      (node (ref "U6") (pin "27") (pinfunction "IREF_27") (pintype "passive"))
    )
    (net (code "184") (name "Net-(U7-IREF)") (class "Default")
      (node (ref "R152") (pin "2") (pinfunction "2_2") (pintype "passive"))
      (node (ref "U7") (pin "27") (pinfunction "IREF_27") (pintype "passive"))
    )
    (net (code "185") (name "Net-(U7-SIN)") (class "Default")
      (node (ref "U7") (pin "5") (pinfunction "SIN_5") (pintype "passive"))
      (node (ref "U8") (pin "24") (pinfunction "SOUT_24") (pintype "passive"))
    )
    (net (code "186") (name "Net-(U8-IREF)") (class "Default")
      (node (ref "R151") (pin "2") (pinfunction "2_2") (pintype "passive"))
      (node (ref "U8") (pin "27") (pinfunction "IREF_27") (pintype "passive"))
    )
    (net (code "187") (name "Net-(U9-IREF)") (class "Default")
      (node (ref "R153") (pin "2") (pinfunction "2_2") (pintype "passive"))
      (node (ref "U9") (pin "27") (pinfunction "IREF_27") (pintype "passive"))
    )
    (net (code "188") (name "VCC") (class "Default")
      (node (ref "C1") (pin "2") (pinfunction "2_2") (pintype "passive"))
      (node (ref "C11") (pin "2") (pinfunction "2_2") (pintype "passive"))
      (node (ref "C2") (pin "2") (pinfunction "2_2") (pintype "passive"))
      (node (ref "C3") (pin "2") (pinfunction "2_2") (pintype "passive"))
      (node (ref "C4") (pin "2") (pinfunction "2_2") (pintype "passive"))
      (node (ref "C6") (pin "2") (pinfunction "2_2") (pintype "passive"))
      (node (ref "C7") (pin "2") (pinfunction "2_2") (pintype "passive"))
      (node (ref "C8") (pin "2") (pinfunction "2_2") (pintype "passive"))
      (node (ref "C9") (pin "2") (pinfunction "2_2") (pintype "passive"))
      (node (ref "R154") (pin "1") (pinfunction "1_1") (pintype "passive"))
      (node (ref "R155") (pin "1") (pinfunction "1_1") (pintype "passive"))
      (node (ref "R156") (pin "1") (pinfunction "1_1") (pintype "passive"))
      (node (ref "R157") (pin "1") (pinfunction "1_1") (pintype "passive"))
      (node (ref "R158") (pin "1") (pinfunction "1_1") (pintype "passive"))
      (node (ref "R159") (pin "1") (pinfunction "1_1") (pintype "passive"))
      (node (ref "R160") (pin "1") (pinfunction "1_1") (pintype "passive"))
      (node (ref "R161") (pin "1") (pinfunction "1_1") (pintype "passive"))
      (node (ref "R162") (pin "1") (pinfunction "1_1") (pintype "passive"))
      (node (ref "U1") (pin "26") (pinfunction "DCPRG_26") (pintype "passive"))
      (node (ref "U1") (pin "28") (pinfunction "VCC_28") (pintype "passive"))
      (node (ref "U2") (pin "26") (pinfunction "DCPRG_26") (pintype "passive"))
      (node (ref "U2") (pin "28") (pinfunction "VCC_28") (pintype "passive"))
      (node (ref "U3") (pin "26") (pinfunction "DCPRG_26") (pintype "passive"))
      (node (ref "U3") (pin "28") (pinfunction "VCC_28") (pintype "passive"))
      (node (ref "U4") (pin "26") (pinfunction "DCPRG_26") (pintype "passive"))
      (node (ref "U4") (pin "28") (pinfunction "VCC_28") (pintype "passive"))
      (node (ref "U5") (pin "26") (pinfunction "DCPRG_26") (pintype "passive"))
      (node (ref "U5") (pin "28") (pinfunction "VCC_28") (pintype "passive"))
      (node (ref "U6") (pin "26") (pinfunction "DCPRG_26") (pintype "passive"))
      (node (ref "U6") (pin "28") (pinfunction "VCC_28") (pintype "passive"))
      (node (ref "U7") (pin "26") (pinfunction "DCPRG_26") (pintype "passive"))
      (node (ref "U7") (pin "28") (pinfunction "VCC_28") (pintype "passive"))
      (node (ref "U8") (pin "26") (pinfunction "DCPRG_26") (pintype "passive"))
      (node (ref "U8") (pin "28") (pinfunction "VCC_28") (pintype "passive"))
      (node (ref "U9") (pin "26") (pinfunction "DCPRG_26") (pintype "passive"))
      (node (ref "U9") (pin "28") (pinfunction "VCC_28") (pintype "passive"))
    )
    (net (code "189") (name "unconnected-(U9-SOUT-Pad24)") (class "Default")
      (node (ref "U9") (pin "24") (pinfunction "SOUT_24") (pintype "passive"))
    )
  )
)
